# MCU_SoM.net
KiCad netlist of a schematic drawn in Altium Designer
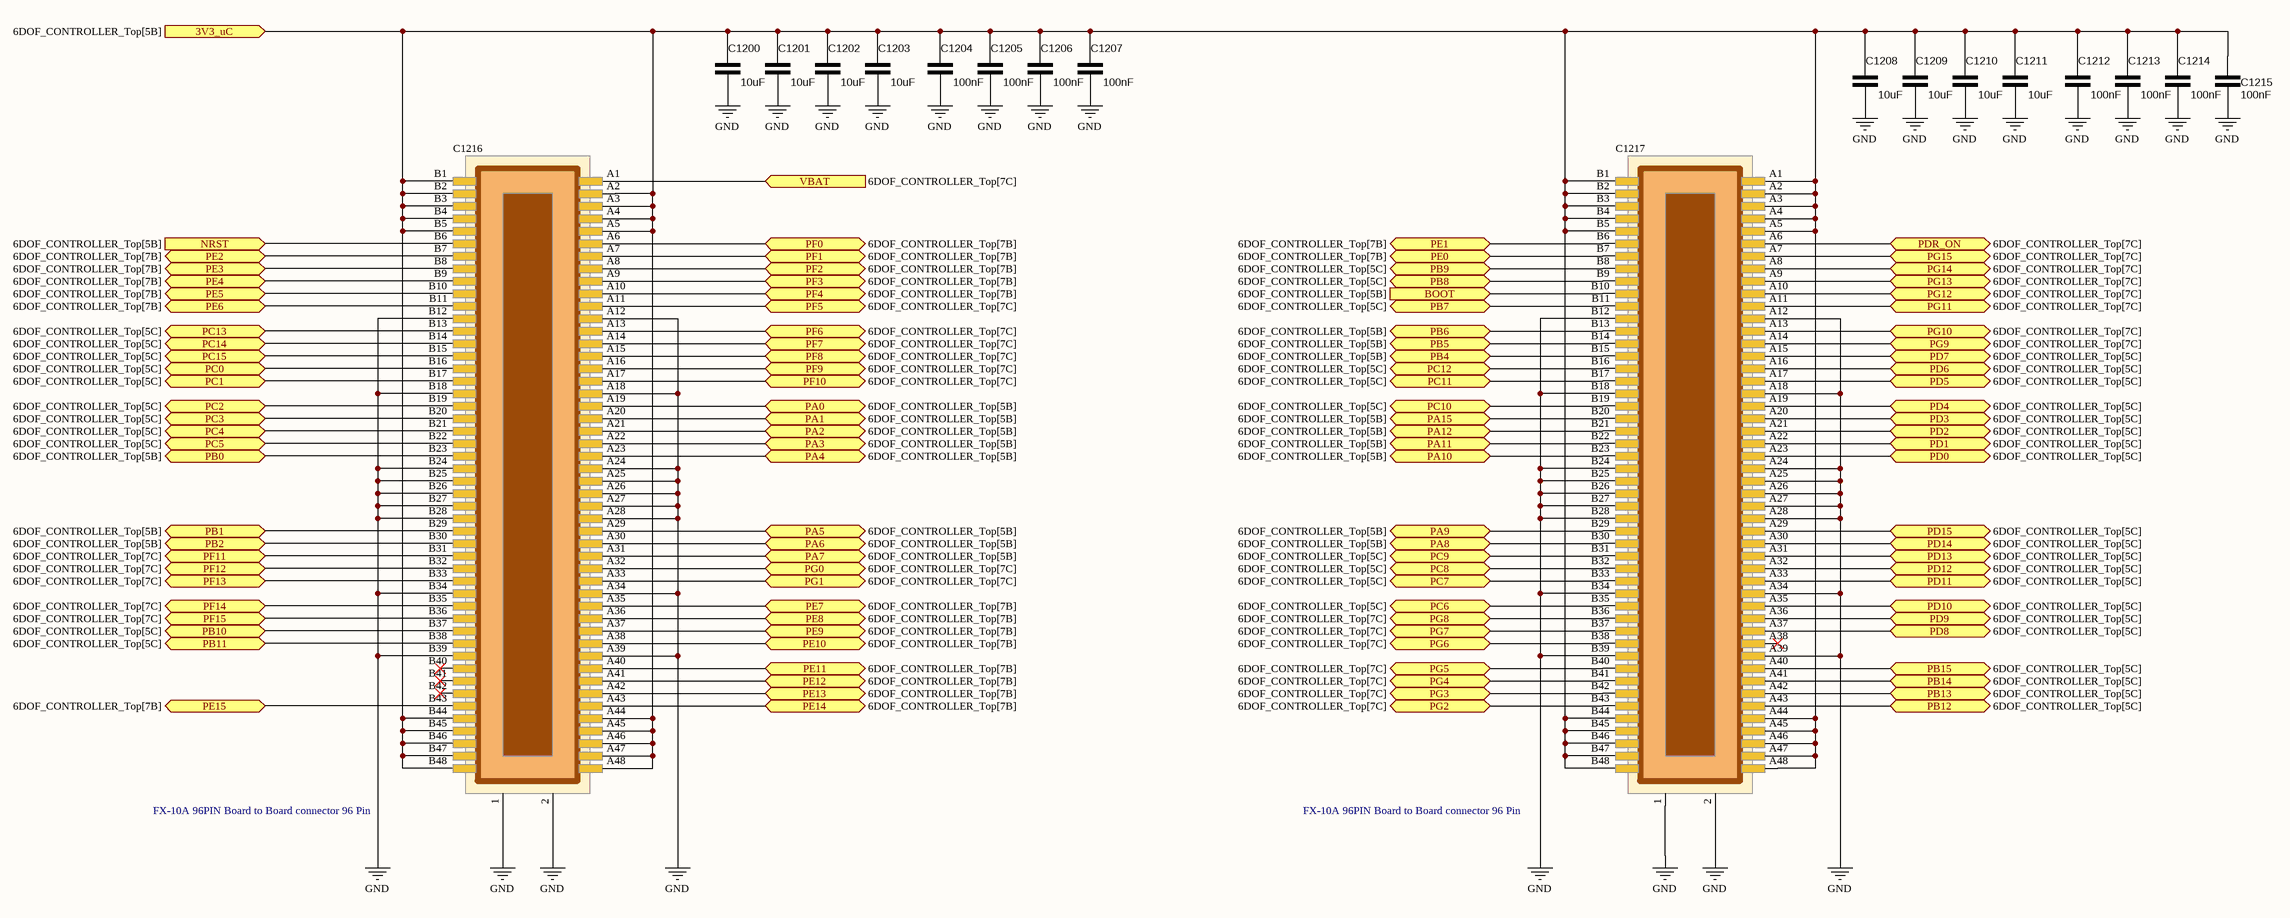
[diagram p0: MCU_SoM.SchDoc]

(export (version "E")
  (design (tool "Eeschema 10.0.6"))
  (components
    (comp (ref "C1200")
      (value "10uF")
      (footprint "CAP_0805")
      (description "10 µF ±10% 25V Ceramic Capacitor X5R 0805 (2012 Metric)")
      (fields (field (name "DIGIKEY PART NUMBER") "445-5984-1-ND"))
      (libsource (lib "CapacitorsIntegrated") (part "C000002"))
    )
    (comp (ref "C1201")
      (value "10uF")
      (footprint "CAP_0805")
      (description "10 µF ±10% 25V Ceramic Capacitor X5R 0805 (2012 Metric)")
      (fields (field (name "DIGIKEY PART NUMBER") "445-5984-1-ND"))
      (libsource (lib "CapacitorsIntegrated") (part "C000002"))
    )
    (comp (ref "C1202")
      (value "10uF")
      (footprint "CAP_0805")
      (description "10 µF ±10% 25V Ceramic Capacitor X5R 0805 (2012 Metric)")
      (fields (field (name "DIGIKEY PART NUMBER") "445-5984-1-ND"))
      (libsource (lib "CapacitorsIntegrated") (part "C000002"))
    )
    (comp (ref "C1203")
      (value "10uF")
      (footprint "CAP_0805")
      (description "10 µF ±10% 25V Ceramic Capacitor X5R 0805 (2012 Metric)")
      (fields (field (name "DIGIKEY PART NUMBER") "445-5984-1-ND"))
      (libsource (lib "CapacitorsIntegrated") (part "C000002"))
    )
    (comp (ref "C1204")
      (value "100nF")
      (footprint "CAP_0603")
      (description "0.1 µF ±10% 25V Ceramic Capacitor X7R 0603 (1608 Metric)")
      (fields (field (name "DIGIKEY PART NUMBER") "478-KAM15AR71E104KTCT-ND"))
      (libsource (lib "CapacitorsIntegrated") (part "C000007"))
    )
    (comp (ref "C1205")
      (value "100nF")
      (footprint "CAP_0603")
      (description "0.1 µF ±10% 25V Ceramic Capacitor X7R 0603 (1608 Metric)")
      (fields (field (name "DIGIKEY PART NUMBER") "478-KAM15AR71E104KTCT-ND"))
      (libsource (lib "CapacitorsIntegrated") (part "C000007"))
    )
    (comp (ref "C1206")
      (value "100nF")
      (footprint "CAP_0603")
      (description "0.1 µF ±10% 25V Ceramic Capacitor X7R 0603 (1608 Metric)")
      (fields (field (name "DIGIKEY PART NUMBER") "478-KAM15AR71E104KTCT-ND"))
      (libsource (lib "CapacitorsIntegrated") (part "C000007"))
    )
    (comp (ref "C1207")
      (value "100nF")
      (footprint "CAP_0603")
      (description "0.1 µF ±10% 25V Ceramic Capacitor X7R 0603 (1608 Metric)")
      (fields (field (name "DIGIKEY PART NUMBER") "478-KAM15AR71E104KTCT-ND"))
      (libsource (lib "CapacitorsIntegrated") (part "C000007"))
    )
    (comp (ref "C1208")
      (value "10uF")
      (footprint "CAP_0805")
      (description "10 µF ±10% 25V Ceramic Capacitor X5R 0805 (2012 Metric)")
      (fields (field (name "DIGIKEY PART NUMBER") "445-5984-1-ND"))
      (libsource (lib "CapacitorsIntegrated") (part "C000002"))
    )
    (comp (ref "C1209")
      (value "10uF")
      (footprint "CAP_0805")
      (description "10 µF ±10% 25V Ceramic Capacitor X5R 0805 (2012 Metric)")
      (fields (field (name "DIGIKEY PART NUMBER") "445-5984-1-ND"))
      (libsource (lib "CapacitorsIntegrated") (part "C000002"))
    )
    (comp (ref "C1210")
      (value "10uF")
      (footprint "CAP_0805")
      (description "10 µF ±10% 25V Ceramic Capacitor X5R 0805 (2012 Metric)")
      (fields (field (name "DIGIKEY PART NUMBER") "445-5984-1-ND"))
      (libsource (lib "CapacitorsIntegrated") (part "C000002"))
    )
    (comp (ref "C1211")
      (value "10uF")
      (footprint "CAP_0805")
      (description "10 µF ±10% 25V Ceramic Capacitor X5R 0805 (2012 Metric)")
      (fields (field (name "DIGIKEY PART NUMBER") "445-5984-1-ND"))
      (libsource (lib "CapacitorsIntegrated") (part "C000002"))
    )
    (comp (ref "C1212")
      (value "100nF")
      (footprint "CAP_0603")
      (description "0.1 µF ±10% 25V Ceramic Capacitor X7R 0603 (1608 Metric)")
      (fields (field (name "DIGIKEY PART NUMBER") "478-KAM15AR71E104KTCT-ND"))
      (libsource (lib "CapacitorsIntegrated") (part "C000007"))
    )
    (comp (ref "C1213")
      (value "100nF")
      (footprint "CAP_0603")
      (description "0.1 µF ±10% 25V Ceramic Capacitor X7R 0603 (1608 Metric)")
      (fields (field (name "DIGIKEY PART NUMBER") "478-KAM15AR71E104KTCT-ND"))
      (libsource (lib "CapacitorsIntegrated") (part "C000007"))
    )
    (comp (ref "C1214")
      (value "100nF")
      (footprint "CAP_0603")
      (description "0.1 µF ±10% 25V Ceramic Capacitor X7R 0603 (1608 Metric)")
      (fields (field (name "DIGIKEY PART NUMBER") "478-KAM15AR71E104KTCT-ND"))
      (libsource (lib "CapacitorsIntegrated") (part "C000007"))
    )
    (comp (ref "C1215")
      (value "100nF")
      (footprint "CAP_0603")
      (description "0.1 µF ±10% 25V Ceramic Capacitor X7R 0603 (1608 Metric)")
      (fields (field (name "DIGIKEY PART NUMBER") "478-KAM15AR71E104KTCT-ND"))
      (libsource (lib "CapacitorsIntegrated") (part "C000007"))
    )
    (comp (ref "C1216")
      (value "FX-10A 96PIN Board to Board connector 96 Pin")
      (footprint "Board To Board Connector - Female")
      (description "CONN RCPT 96POS SMD GOLD - FEMALE")
      (fields (field (name "DIGIKEY PART NUMBER") "H122463-ND"))
      (libsource (lib "ElectroMechanical") (part "00000016"))
    )
    (comp (ref "C1217")
      (value "FX-10A 96PIN Board to Board connector 96 Pin")
      (footprint "Board To Board Connector - Female")
      (description "CONN RCPT 96POS SMD GOLD - FEMALE")
      (fields (field (name "DIGIKEY PART NUMBER") "H122463-ND"))
      (libsource (lib "ElectroMechanical") (part "00000016"))
    )
  )
  (nets
    (net (code "1") (name "/3V3_uC") (class "Default")
      (node (ref "C1200") (pin "2") (pinfunction "2_2") (pintype "passive"))
      (node (ref "C1201") (pin "2") (pinfunction "2_2") (pintype "passive"))
      (node (ref "C1202") (pin "2") (pinfunction "2_2") (pintype "passive"))
      (node (ref "C1203") (pin "2") (pinfunction "2_2") (pintype "passive"))
      (node (ref "C1204") (pin "2") (pinfunction "2_2") (pintype "passive"))
      (node (ref "C1205") (pin "2") (pinfunction "2_2") (pintype "passive"))
      (node (ref "C1206") (pin "2") (pinfunction "2_2") (pintype "passive"))
      (node (ref "C1207") (pin "2") (pinfunction "2_2") (pintype "passive"))
      (node (ref "C1208") (pin "2") (pinfunction "2_2") (pintype "passive"))
      (node (ref "C1209") (pin "2") (pinfunction "2_2") (pintype "passive"))
      (node (ref "C1210") (pin "2") (pinfunction "2_2") (pintype "passive"))
      (node (ref "C1211") (pin "2") (pinfunction "2_2") (pintype "passive"))
      (node (ref "C1212") (pin "2") (pinfunction "2_2") (pintype "passive"))
      (node (ref "C1213") (pin "2") (pinfunction "2_2") (pintype "passive"))
      (node (ref "C1214") (pin "2") (pinfunction "2_2") (pintype "passive"))
      (node (ref "C1215") (pin "2") (pinfunction "2_2") (pintype "passive"))
      (node (ref "C1216") (pin "A2") (pinfunction "2_A2") (pintype "passive"))
      (node (ref "C1216") (pin "A3") (pinfunction "3_A3") (pintype "passive"))
      (node (ref "C1216") (pin "A4") (pinfunction "4_A4") (pintype "passive"))
      (node (ref "C1216") (pin "A44") (pinfunction "44_A44") (pintype "passive"))
      (node (ref "C1216") (pin "A45") (pinfunction "45_A45") (pintype "passive"))
      (node (ref "C1216") (pin "A46") (pinfunction "46_A46") (pintype "passive"))
      (node (ref "C1216") (pin "A47") (pinfunction "47_A47") (pintype "passive"))
      (node (ref "C1216") (pin "A48") (pinfunction "48_A48") (pintype "passive"))
      (node (ref "C1216") (pin "A5") (pinfunction "5_A5") (pintype "passive"))
      (node (ref "C1216") (pin "B1") (pinfunction "1_B1") (pintype "passive"))
      (node (ref "C1216") (pin "B2") (pinfunction "2_B2") (pintype "passive"))
      (node (ref "C1216") (pin "B3") (pinfunction "3_B3") (pintype "passive"))
      (node (ref "C1216") (pin "B4") (pinfunction "4_B4") (pintype "passive"))
      (node (ref "C1216") (pin "B44") (pinfunction "44_B44") (pintype "passive"))
      (node (ref "C1216") (pin "B45") (pinfunction "45_B45") (pintype "passive"))
      (node (ref "C1216") (pin "B46") (pinfunction "46_B46") (pintype "passive"))
      (node (ref "C1216") (pin "B47") (pinfunction "47_B47") (pintype "passive"))
      (node (ref "C1216") (pin "B48") (pinfunction "48_B48") (pintype "passive"))
      (node (ref "C1216") (pin "B5") (pinfunction "5_B5") (pintype "passive"))
      (node (ref "C1217") (pin "A1") (pinfunction "1_A1") (pintype "passive"))
      (node (ref "C1217") (pin "A2") (pinfunction "2_A2") (pintype "passive"))
      (node (ref "C1217") (pin "A3") (pinfunction "3_A3") (pintype "passive"))
      (node (ref "C1217") (pin "A4") (pinfunction "4_A4") (pintype "passive"))
      (node (ref "C1217") (pin "A44") (pinfunction "44_A44") (pintype "passive"))
      (node (ref "C1217") (pin "A45") (pinfunction "45_A45") (pintype "passive"))
      (node (ref "C1217") (pin "A46") (pinfunction "46_A46") (pintype "passive"))
      (node (ref "C1217") (pin "A47") (pinfunction "47_A47") (pintype "passive"))
      (node (ref "C1217") (pin "A48") (pinfunction "48_A48") (pintype "passive"))
      (node (ref "C1217") (pin "A5") (pinfunction "5_A5") (pintype "passive"))
      (node (ref "C1217") (pin "B1") (pinfunction "1_B1") (pintype "passive"))
      (node (ref "C1217") (pin "B2") (pinfunction "2_B2") (pintype "passive"))
      (node (ref "C1217") (pin "B3") (pinfunction "3_B3") (pintype "passive"))
      (node (ref "C1217") (pin "B4") (pinfunction "4_B4") (pintype "passive"))
      (node (ref "C1217") (pin "B44") (pinfunction "44_B44") (pintype "passive"))
      (node (ref "C1217") (pin "B45") (pinfunction "45_B45") (pintype "passive"))
      (node (ref "C1217") (pin "B46") (pinfunction "46_B46") (pintype "passive"))
      (node (ref "C1217") (pin "B47") (pinfunction "47_B47") (pintype "passive"))
      (node (ref "C1217") (pin "B48") (pinfunction "48_B48") (pintype "passive"))
      (node (ref "C1217") (pin "B5") (pinfunction "5_B5") (pintype "passive"))
    )
    (net (code "2") (name "/BOOT") (class "Default")
      (node (ref "C1217") (pin "B10") (pinfunction "10_B10") (pintype "passive"))
    )
    (net (code "3") (name "/NRST") (class "Default")
      (node (ref "C1216") (pin "B6") (pinfunction "6_B6") (pintype "passive"))
    )
    (net (code "4") (name "/PA0") (class "Default")
      (node (ref "C1216") (pin "A19") (pinfunction "19_A19") (pintype "passive"))
    )
    (net (code "5") (name "/PA1") (class "Default")
      (node (ref "C1216") (pin "A20") (pinfunction "20_A20") (pintype "passive"))
    )
    (net (code "6") (name "/PA2") (class "Default")
      (node (ref "C1216") (pin "A21") (pinfunction "21_A21") (pintype "passive"))
    )
    (net (code "7") (name "/PA3") (class "Default")
      (node (ref "C1216") (pin "A22") (pinfunction "22_A22") (pintype "passive"))
    )
    (net (code "8") (name "/PA4") (class "Default")
      (node (ref "C1216") (pin "A23") (pinfunction "23_A23") (pintype "passive"))
    )
    (net (code "9") (name "/PA5") (class "Default")
      (node (ref "C1216") (pin "A29") (pinfunction "29_A29") (pintype "passive"))
    )
    (net (code "10") (name "/PA6") (class "Default")
      (node (ref "C1216") (pin "A30") (pinfunction "30_A30") (pintype "passive"))
    )
    (net (code "11") (name "/PA7") (class "Default")
      (node (ref "C1216") (pin "A31") (pinfunction "31_A31") (pintype "passive"))
    )
    (net (code "12") (name "/PA8") (class "Default")
      (node (ref "C1217") (pin "B30") (pinfunction "30_B30") (pintype "passive"))
    )
    (net (code "13") (name "/PA9") (class "Default")
      (node (ref "C1217") (pin "B29") (pinfunction "29_B29") (pintype "passive"))
    )
    (net (code "14") (name "/PA10") (class "Default")
      (node (ref "C1217") (pin "B23") (pinfunction "23_B23") (pintype "passive"))
    )
    (net (code "15") (name "/PA11") (class "Default")
      (node (ref "C1217") (pin "B22") (pinfunction "22_B22") (pintype "passive"))
    )
    (net (code "16") (name "/PA12") (class "Default")
      (node (ref "C1217") (pin "B21") (pinfunction "21_B21") (pintype "passive"))
    )
    (net (code "17") (name "/PA15") (class "Default")
      (node (ref "C1217") (pin "B20") (pinfunction "20_B20") (pintype "passive"))
    )
    (net (code "18") (name "/PB0") (class "Default")
      (node (ref "C1216") (pin "B23") (pinfunction "23_B23") (pintype "passive"))
    )
    (net (code "19") (name "/PB1") (class "Default")
      (node (ref "C1216") (pin "B29") (pinfunction "29_B29") (pintype "passive"))
    )
    (net (code "20") (name "/PB2") (class "Default")
      (node (ref "C1216") (pin "B30") (pinfunction "30_B30") (pintype "passive"))
    )
    (net (code "21") (name "/PB4") (class "Default")
      (node (ref "C1217") (pin "B15") (pinfunction "15_B15") (pintype "passive"))
    )
    (net (code "22") (name "/PB5") (class "Default")
      (node (ref "C1217") (pin "B14") (pinfunction "14_B14") (pintype "passive"))
    )
    (net (code "23") (name "/PB6") (class "Default")
      (node (ref "C1217") (pin "B13") (pinfunction "13_B13") (pintype "passive"))
    )
    (net (code "24") (name "/PB7") (class "Default")
      (node (ref "C1217") (pin "B11") (pinfunction "11_B11") (pintype "passive"))
    )
    (net (code "25") (name "/PB8") (class "Default")
      (node (ref "C1217") (pin "B9") (pinfunction "9_B9") (pintype "passive"))
    )
    (net (code "26") (name "/PB9") (class "Default")
      (node (ref "C1217") (pin "B8") (pinfunction "8_B8") (pintype "passive"))
    )
    (net (code "27") (name "/PB10") (class "Default")
      (node (ref "C1216") (pin "B37") (pinfunction "37_B37") (pintype "passive"))
    )
    (net (code "28") (name "/PB11") (class "Default")
      (node (ref "C1216") (pin "B38") (pinfunction "38_B38") (pintype "passive"))
    )
    (net (code "29") (name "/PB12") (class "Default")
      (node (ref "C1217") (pin "A43") (pinfunction "43_A43") (pintype "passive"))
    )
    (net (code "30") (name "/PB13") (class "Default")
      (node (ref "C1217") (pin "A42") (pinfunction "42_A42") (pintype "passive"))
    )
    (net (code "31") (name "/PB14") (class "Default")
      (node (ref "C1217") (pin "A41") (pinfunction "41_A41") (pintype "passive"))
    )
    (net (code "32") (name "/PB15") (class "Default")
      (node (ref "C1217") (pin "A40") (pinfunction "40_A40") (pintype "passive"))
    )
    (net (code "33") (name "/PC0") (class "Default")
      (node (ref "C1216") (pin "B16") (pinfunction "16_B16") (pintype "passive"))
    )
    (net (code "34") (name "/PC1") (class "Default")
      (node (ref "C1216") (pin "B17") (pinfunction "17_B17") (pintype "passive"))
    )
    (net (code "35") (name "/PC2") (class "Default")
      (node (ref "C1216") (pin "B19") (pinfunction "19_B19") (pintype "passive"))
    )
    (net (code "36") (name "/PC3") (class "Default")
      (node (ref "C1216") (pin "B20") (pinfunction "20_B20") (pintype "passive"))
    )
    (net (code "37") (name "/PC4") (class "Default")
      (node (ref "C1216") (pin "B21") (pinfunction "21_B21") (pintype "passive"))
    )
    (net (code "38") (name "/PC5") (class "Default")
      (node (ref "C1216") (pin "B22") (pinfunction "22_B22") (pintype "passive"))
    )
    (net (code "39") (name "/PC6") (class "Default")
      (node (ref "C1217") (pin "B35") (pinfunction "35_B35") (pintype "passive"))
    )
    (net (code "40") (name "/PC7") (class "Default")
      (node (ref "C1217") (pin "B33") (pinfunction "33_B33") (pintype "passive"))
    )
    (net (code "41") (name "/PC8") (class "Default")
      (node (ref "C1217") (pin "B32") (pinfunction "32_B32") (pintype "passive"))
    )
    (net (code "42") (name "/PC9") (class "Default")
      (node (ref "C1217") (pin "B31") (pinfunction "31_B31") (pintype "passive"))
    )
    (net (code "43") (name "/PC10") (class "Default")
      (node (ref "C1217") (pin "B19") (pinfunction "19_B19") (pintype "passive"))
    )
    (net (code "44") (name "/PC11") (class "Default")
      (node (ref "C1217") (pin "B17") (pinfunction "17_B17") (pintype "passive"))
    )
    (net (code "45") (name "/PC12") (class "Default")
      (node (ref "C1217") (pin "B16") (pinfunction "16_B16") (pintype "passive"))
    )
    (net (code "46") (name "/PC13") (class "Default")
      (node (ref "C1216") (pin "B13") (pinfunction "13_B13") (pintype "passive"))
    )
    (net (code "47") (name "/PC14") (class "Default")
      (node (ref "C1216") (pin "B14") (pinfunction "14_B14") (pintype "passive"))
    )
    (net (code "48") (name "/PC15") (class "Default")
      (node (ref "C1216") (pin "B15") (pinfunction "15_B15") (pintype "passive"))
    )
    (net (code "49") (name "/PD0") (class "Default")
      (node (ref "C1217") (pin "A23") (pinfunction "23_A23") (pintype "passive"))
    )
    (net (code "50") (name "/PD1") (class "Default")
      (node (ref "C1217") (pin "A22") (pinfunction "22_A22") (pintype "passive"))
    )
    (net (code "51") (name "/PD2") (class "Default")
      (node (ref "C1217") (pin "A21") (pinfunction "21_A21") (pintype "passive"))
    )
    (net (code "52") (name "/PD3") (class "Default")
      (node (ref "C1217") (pin "A20") (pinfunction "20_A20") (pintype "passive"))
    )
    (net (code "53") (name "/PD4") (class "Default")
      (node (ref "C1217") (pin "A19") (pinfunction "19_A19") (pintype "passive"))
    )
    (net (code "54") (name "/PD5") (class "Default")
      (node (ref "C1217") (pin "A17") (pinfunction "17_A17") (pintype "passive"))
    )
    (net (code "55") (name "/PD6") (class "Default")
      (node (ref "C1217") (pin "A16") (pinfunction "16_A16") (pintype "passive"))
    )
    (net (code "56") (name "/PD7") (class "Default")
      (node (ref "C1217") (pin "A15") (pinfunction "15_A15") (pintype "passive"))
    )
    (net (code "57") (name "/PD8") (class "Default")
      (node (ref "C1217") (pin "A37") (pinfunction "37_A37") (pintype "passive"))
    )
    (net (code "58") (name "/PD9") (class "Default")
      (node (ref "C1217") (pin "A36") (pinfunction "36_A36") (pintype "passive"))
    )
    (net (code "59") (name "/PD10") (class "Default")
      (node (ref "C1217") (pin "A35") (pinfunction "35_A35") (pintype "passive"))
    )
    (net (code "60") (name "/PD11") (class "Default")
      (node (ref "C1217") (pin "A33") (pinfunction "33_A33") (pintype "passive"))
    )
    (net (code "61") (name "/PD12") (class "Default")
      (node (ref "C1217") (pin "A32") (pinfunction "32_A32") (pintype "passive"))
    )
    (net (code "62") (name "/PD13") (class "Default")
      (node (ref "C1217") (pin "A31") (pinfunction "31_A31") (pintype "passive"))
    )
    (net (code "63") (name "/PD14") (class "Default")
      (node (ref "C1217") (pin "A30") (pinfunction "30_A30") (pintype "passive"))
    )
    (net (code "64") (name "/PD15") (class "Default")
      (node (ref "C1217") (pin "A29") (pinfunction "29_A29") (pintype "passive"))
    )
    (net (code "65") (name "/PDR_ON") (class "Default")
      (node (ref "C1217") (pin "A6") (pinfunction "6_A6") (pintype "passive"))
    )
    (net (code "66") (name "/PE0") (class "Default")
      (node (ref "C1217") (pin "B7") (pinfunction "7_B7") (pintype "passive"))
    )
    (net (code "67") (name "/PE1") (class "Default")
      (node (ref "C1217") (pin "B6") (pinfunction "6_B6") (pintype "passive"))
    )
    (net (code "68") (name "/PE2") (class "Default")
      (node (ref "C1216") (pin "B7") (pinfunction "7_B7") (pintype "passive"))
    )
    (net (code "69") (name "/PE3") (class "Default")
      (node (ref "C1216") (pin "B8") (pinfunction "8_B8") (pintype "passive"))
    )
    (net (code "70") (name "/PE4") (class "Default")
      (node (ref "C1216") (pin "B9") (pinfunction "9_B9") (pintype "passive"))
    )
    (net (code "71") (name "/PE5") (class "Default")
      (node (ref "C1216") (pin "B10") (pinfunction "10_B10") (pintype "passive"))
    )
    (net (code "72") (name "/PE6") (class "Default")
      (node (ref "C1216") (pin "B11") (pinfunction "11_B11") (pintype "passive"))
    )
    (net (code "73") (name "/PE7") (class "Default")
      (node (ref "C1216") (pin "A35") (pinfunction "35_A35") (pintype "passive"))
    )
    (net (code "74") (name "/PE8") (class "Default")
      (node (ref "C1216") (pin "A36") (pinfunction "36_A36") (pintype "passive"))
    )
    (net (code "75") (name "/PE9") (class "Default")
      (node (ref "C1216") (pin "A37") (pinfunction "37_A37") (pintype "passive"))
    )
    (net (code "76") (name "/PE10") (class "Default")
      (node (ref "C1216") (pin "A38") (pinfunction "38_A38") (pintype "passive"))
    )
    (net (code "77") (name "/PE11") (class "Default")
      (node (ref "C1216") (pin "A40") (pinfunction "40_A40") (pintype "passive"))
    )
    (net (code "78") (name "/PE12") (class "Default")
      (node (ref "C1216") (pin "A41") (pinfunction "41_A41") (pintype "passive"))
    )
    (net (code "79") (name "/PE13") (class "Default")
      (node (ref "C1216") (pin "A42") (pinfunction "42_A42") (pintype "passive"))
    )
    (net (code "80") (name "/PE14") (class "Default")
      (node (ref "C1216") (pin "A43") (pinfunction "43_A43") (pintype "passive"))
    )
    (net (code "81") (name "/PE15") (class "Default")
      (node (ref "C1216") (pin "B43") (pinfunction "43_B43") (pintype "passive"))
    )
    (net (code "82") (name "/PF0") (class "Default")
      (node (ref "C1216") (pin "A6") (pinfunction "6_A6") (pintype "passive"))
    )
    (net (code "83") (name "/PF1") (class "Default")
      (node (ref "C1216") (pin "A7") (pinfunction "7_A7") (pintype "passive"))
    )
    (net (code "84") (name "/PF2") (class "Default")
      (node (ref "C1216") (pin "A8") (pinfunction "8_A8") (pintype "passive"))
    )
    (net (code "85") (name "/PF3") (class "Default")
      (node (ref "C1216") (pin "A9") (pinfunction "9_A9") (pintype "passive"))
    )
    (net (code "86") (name "/PF4") (class "Default")
      (node (ref "C1216") (pin "A10") (pinfunction "10_A10") (pintype "passive"))
    )
    (net (code "87") (name "/PF5") (class "Default")
      (node (ref "C1216") (pin "A11") (pinfunction "11_A11") (pintype "passive"))
    )
    (net (code "88") (name "/PF6") (class "Default")
      (node (ref "C1216") (pin "A13") (pinfunction "13_A13") (pintype "passive"))
    )
    (net (code "89") (name "/PF7") (class "Default")
      (node (ref "C1216") (pin "A14") (pinfunction "14_A14") (pintype "passive"))
    )
    (net (code "90") (name "/PF8") (class "Default")
      (node (ref "C1216") (pin "A15") (pinfunction "15_A15") (pintype "passive"))
    )
    (net (code "91") (name "/PF9") (class "Default")
      (node (ref "C1216") (pin "A16") (pinfunction "16_A16") (pintype "passive"))
    )
    (net (code "92") (name "/PF10") (class "Default")
      (node (ref "C1216") (pin "A17") (pinfunction "17_A17") (pintype "passive"))
    )
    (net (code "93") (name "/PF11") (class "Default")
      (node (ref "C1216") (pin "B31") (pinfunction "31_B31") (pintype "passive"))
    )
    (net (code "94") (name "/PF12") (class "Default")
      (node (ref "C1216") (pin "B32") (pinfunction "32_B32") (pintype "passive"))
    )
    (net (code "95") (name "/PF13") (class "Default")
      (node (ref "C1216") (pin "B33") (pinfunction "33_B33") (pintype "passive"))
    )
    (net (code "96") (name "/PF14") (class "Default")
      (node (ref "C1216") (pin "B35") (pinfunction "35_B35") (pintype "passive"))
    )
    (net (code "97") (name "/PF15") (class "Default")
      (node (ref "C1216") (pin "B36") (pinfunction "36_B36") (pintype "passive"))
    )
    (net (code "98") (name "/PG0") (class "Default")
      (node (ref "C1216") (pin "A32") (pinfunction "32_A32") (pintype "passive"))
    )
    (net (code "99") (name "/PG1") (class "Default")
      (node (ref "C1216") (pin "A33") (pinfunction "33_A33") (pintype "passive"))
    )
    (net (code "100") (name "/PG2") (class "Default")
      (node (ref "C1217") (pin "B43") (pinfunction "43_B43") (pintype "passive"))
    )
    (net (code "101") (name "/PG3") (class "Default")
      (node (ref "C1217") (pin "B42") (pinfunction "42_B42") (pintype "passive"))
    )
    (net (code "102") (name "/PG4") (class "Default")
      (node (ref "C1217") (pin "B41") (pinfunction "41_B41") (pintype "passive"))
    )
    (net (code "103") (name "/PG5") (class "Default")
      (node (ref "C1217") (pin "B40") (pinfunction "40_B40") (pintype "passive"))
    )
    (net (code "104") (name "/PG6") (class "Default")
      (node (ref "C1217") (pin "B38") (pinfunction "38_B38") (pintype "passive"))
    )
    (net (code "105") (name "/PG7") (class "Default")
      (node (ref "C1217") (pin "B37") (pinfunction "37_B37") (pintype "passive"))
    )
    (net (code "106") (name "/PG8") (class "Default")
      (node (ref "C1217") (pin "B36") (pinfunction "36_B36") (pintype "passive"))
    )
    (net (code "107") (name "/PG9") (class "Default")
      (node (ref "C1217") (pin "A14") (pinfunction "14_A14") (pintype "passive"))
    )
    (net (code "108") (name "/PG10") (class "Default")
      (node (ref "C1217") (pin "A13") (pinfunction "13_A13") (pintype "passive"))
    )
    (net (code "109") (name "/PG11") (class "Default")
      (node (ref "C1217") (pin "A11") (pinfunction "11_A11") (pintype "passive"))
    )
    (net (code "110") (name "/PG12") (class "Default")
      (node (ref "C1217") (pin "A10") (pinfunction "10_A10") (pintype "passive"))
    )
    (net (code "111") (name "/PG13") (class "Default")
      (node (ref "C1217") (pin "A9") (pinfunction "9_A9") (pintype "passive"))
    )
    (net (code "112") (name "/PG14") (class "Default")
      (node (ref "C1217") (pin "A8") (pinfunction "8_A8") (pintype "passive"))
    )
    (net (code "113") (name "/PG15") (class "Default")
      (node (ref "C1217") (pin "A7") (pinfunction "7_A7") (pintype "passive"))
    )
    (net (code "114") (name "/VBAT") (class "Default")
      (node (ref "C1216") (pin "A1") (pinfunction "1_A1") (pintype "passive"))
    )
    (net (code "115") (name "GND") (class "Default")
      (node (ref "C1200") (pin "1") (pinfunction "1_1") (pintype "passive"))
      (node (ref "C1201") (pin "1") (pinfunction "1_1") (pintype "passive"))
      (node (ref "C1202") (pin "1") (pinfunction "1_1") (pintype "passive"))
      (node (ref "C1203") (pin "1") (pinfunction "1_1") (pintype "passive"))
      (node (ref "C1204") (pin "1") (pinfunction "1_1") (pintype "passive"))
      (node (ref "C1205") (pin "1") (pinfunction "1_1") (pintype "passive"))
      (node (ref "C1206") (pin "1") (pinfunction "1_1") (pintype "passive"))
      (node (ref "C1207") (pin "1") (pinfunction "1_1") (pintype "passive"))
      (node (ref "C1208") (pin "1") (pinfunction "1_1") (pintype "passive"))
      (node (ref "C1209") (pin "1") (pinfunction "1_1") (pintype "passive"))
      (node (ref "C1210") (pin "1") (pinfunction "1_1") (pintype "passive"))
      (node (ref "C1211") (pin "1") (pinfunction "1_1") (pintype "passive"))
      (node (ref "C1212") (pin "1") (pinfunction "1_1") (pintype "passive"))
      (node (ref "C1213") (pin "1") (pinfunction "1_1") (pintype "passive"))
      (node (ref "C1214") (pin "1") (pinfunction "1_1") (pintype "passive"))
      (node (ref "C1215") (pin "1") (pinfunction "1_1") (pintype "passive"))
      (node (ref "C1216") (pin "1") (pinfunction "1_1") (pintype "passive"))
      (node (ref "C1216") (pin "2") (pinfunction "2_2") (pintype "passive"))
      (node (ref "C1216") (pin "A12") (pinfunction "12_A12") (pintype "passive"))
      (node (ref "C1216") (pin "A18") (pinfunction "18_A18") (pintype "passive"))
      (node (ref "C1216") (pin "A24") (pinfunction "24_A24") (pintype "passive"))
      (node (ref "C1216") (pin "A25") (pinfunction "25_A25") (pintype "passive"))
      (node (ref "C1216") (pin "A26") (pinfunction "26_A26") (pintype "passive"))
      (node (ref "C1216") (pin "A27") (pinfunction "27_A27") (pintype "passive"))
      (node (ref "C1216") (pin "A28") (pinfunction "28_A28") (pintype "passive"))
      (node (ref "C1216") (pin "A34") (pinfunction "34_A34") (pintype "passive"))
      (node (ref "C1216") (pin "A39") (pinfunction "39_A39") (pintype "passive"))
      (node (ref "C1216") (pin "B12") (pinfunction "12_B12") (pintype "passive"))
      (node (ref "C1216") (pin "B18") (pinfunction "18_B18") (pintype "passive"))
      (node (ref "C1216") (pin "B24") (pinfunction "24_B24") (pintype "passive"))
      (node (ref "C1216") (pin "B25") (pinfunction "25_B25") (pintype "passive"))
      (node (ref "C1216") (pin "B26") (pinfunction "26_B26") (pintype "passive"))
      (node (ref "C1216") (pin "B27") (pinfunction "27_B27") (pintype "passive"))
      (node (ref "C1216") (pin "B28") (pinfunction "28_B28") (pintype "passive"))
      (node (ref "C1216") (pin "B34") (pinfunction "34_B34") (pintype "passive"))
      (node (ref "C1216") (pin "B39") (pinfunction "39_B39") (pintype "passive"))
      (node (ref "C1217") (pin "1") (pinfunction "1_1") (pintype "passive"))
      (node (ref "C1217") (pin "2") (pinfunction "2_2") (pintype "passive"))
      (node (ref "C1217") (pin "A12") (pinfunction "12_A12") (pintype "passive"))
      (node (ref "C1217") (pin "A18") (pinfunction "18_A18") (pintype "passive"))
      (node (ref "C1217") (pin "A24") (pinfunction "24_A24") (pintype "passive"))
      (node (ref "C1217") (pin "A25") (pinfunction "25_A25") (pintype "passive"))
      (node (ref "C1217") (pin "A26") (pinfunction "26_A26") (pintype "passive"))
      (node (ref "C1217") (pin "A27") (pinfunction "27_A27") (pintype "passive"))
      (node (ref "C1217") (pin "A28") (pinfunction "28_A28") (pintype "passive"))
      (node (ref "C1217") (pin "A34") (pinfunction "34_A34") (pintype "passive"))
      (node (ref "C1217") (pin "A39") (pinfunction "39_A39") (pintype "passive"))
      (node (ref "C1217") (pin "B12") (pinfunction "12_B12") (pintype "passive"))
      (node (ref "C1217") (pin "B18") (pinfunction "18_B18") (pintype "passive"))
      (node (ref "C1217") (pin "B24") (pinfunction "24_B24") (pintype "passive"))
      (node (ref "C1217") (pin "B25") (pinfunction "25_B25") (pintype "passive"))
      (node (ref "C1217") (pin "B26") (pinfunction "26_B26") (pintype "passive"))
      (node (ref "C1217") (pin "B27") (pinfunction "27_B27") (pintype "passive"))
      (node (ref "C1217") (pin "B28") (pinfunction "28_B28") (pintype "passive"))
      (node (ref "C1217") (pin "B34") (pinfunction "34_B34") (pintype "passive"))
      (node (ref "C1217") (pin "B39") (pinfunction "39_B39") (pintype "passive"))
    )
    (net (code "116") (name "unconnected-(C1216-40-PadB40)") (class "Default")
      (node (ref "C1216") (pin "B40") (pinfunction "40_B40") (pintype "passive+no_connect"))
    )
    (net (code "117") (name "unconnected-(C1216-41-PadB41)") (class "Default")
      (node (ref "C1216") (pin "B41") (pinfunction "41_B41") (pintype "passive+no_connect"))
    )
    (net (code "118") (name "unconnected-(C1216-42-PadB42)") (class "Default")
      (node (ref "C1216") (pin "B42") (pinfunction "42_B42") (pintype "passive+no_connect"))
    )
    (net (code "119") (name "unconnected-(C1217-38-PadA38)") (class "Default")
      (node (ref "C1217") (pin "A38") (pinfunction "38_A38") (pintype "passive+no_connect"))
    )
  )
)
